# TRV_ANAREN_V0_3.net
KiCad netlist of a schematic drawn in EAGLE
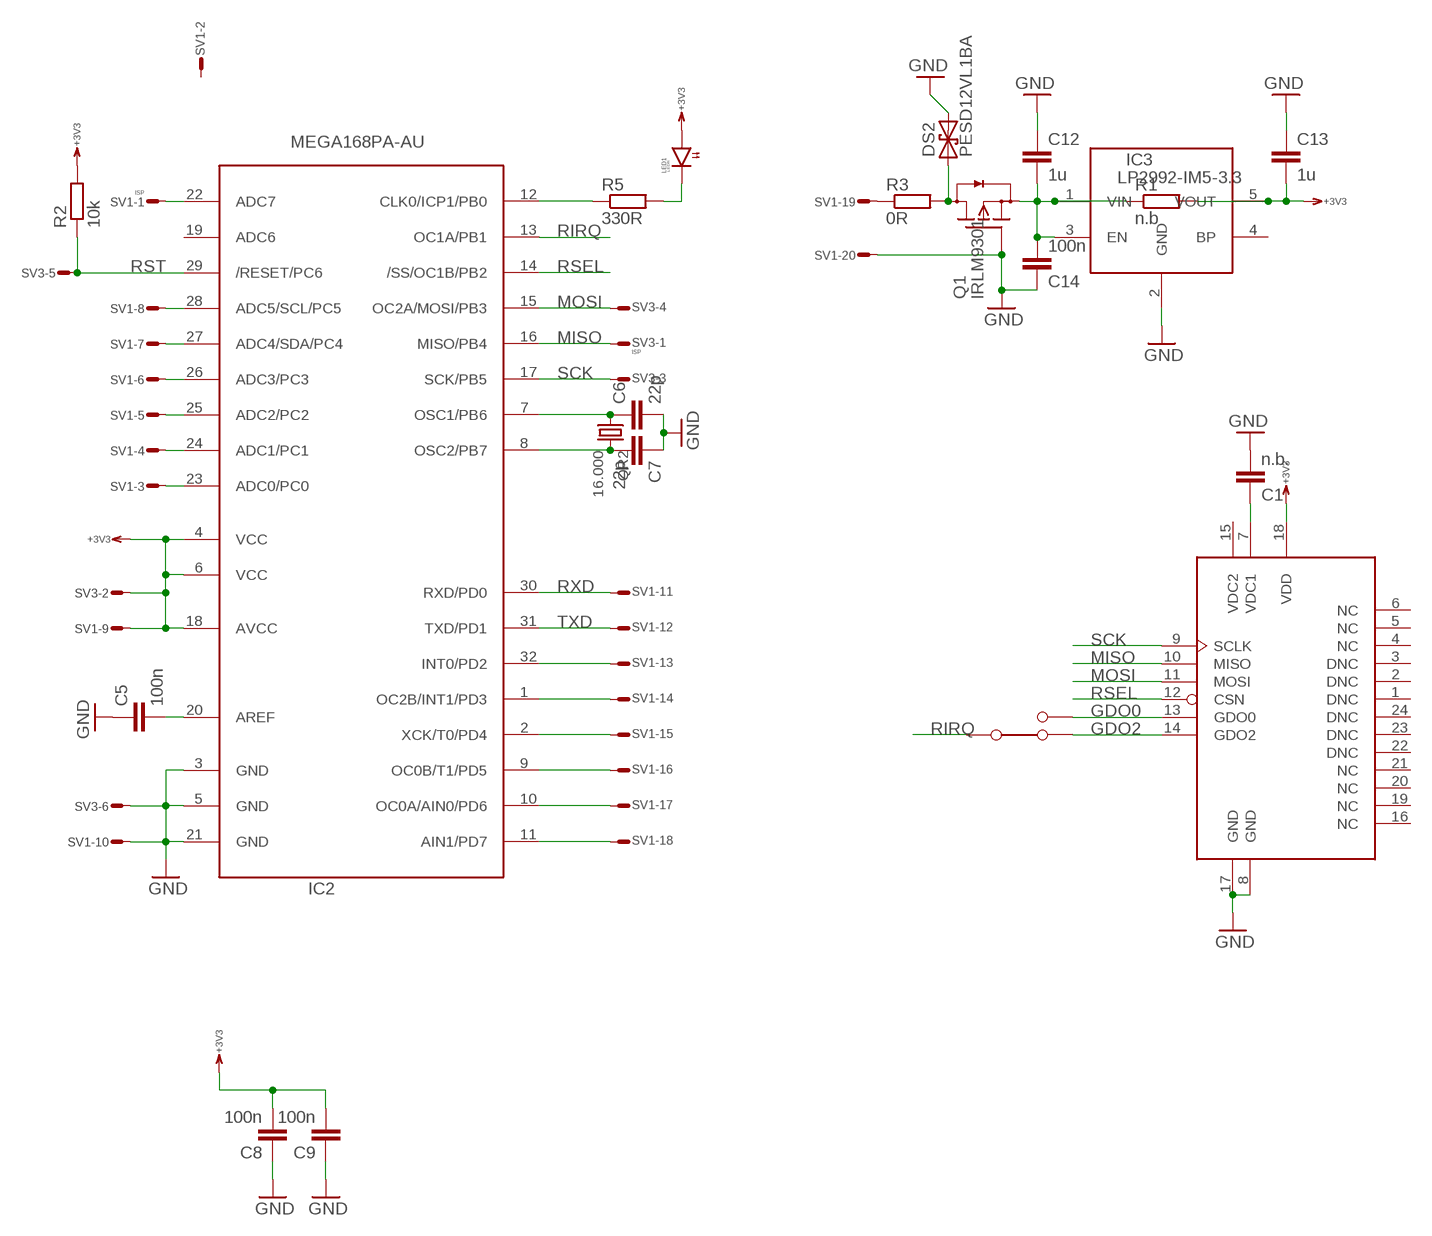
[diagram p0: schematic, sheet 1]

(export (version "E")
  (design (tool "Eeschema 10.0.6"))
  (components
    (comp (ref "BR1") (value "BR") (footprint "eagle-import:BR") (libsource (lib "eagle-import") (part "BR")))
    (comp (ref "C1")
      (value "n.b.")
      (footprint "eagle-import:0603")
      (libsource (lib "eagle-import") (part "C0603"))
    )
    (comp (ref "C5")
      (value "100n")
      (footprint "eagle-import:0603")
      (libsource (lib "eagle-import") (part "C0603"))
    )
    (comp (ref "C6")
      (value "22p")
      (footprint "eagle-import:0603")
      (libsource (lib "eagle-import") (part "C0603"))
    )
    (comp (ref "C7")
      (value "22p")
      (footprint "eagle-import:0603")
      (libsource (lib "eagle-import") (part "C0603"))
    )
    (comp (ref "C8")
      (value "100n")
      (footprint "eagle-import:0603")
      (libsource (lib "eagle-import") (part "C0603"))
    )
    (comp (ref "C9")
      (value "100n")
      (footprint "eagle-import:0603")
      (libsource (lib "eagle-import") (part "C0603"))
    )
    (comp (ref "C12")
      (value "1u")
      (footprint "eagle-import:0603")
      (libsource (lib "eagle-import") (part "C0603"))
    )
    (comp (ref "C13")
      (value "1u")
      (footprint "eagle-import:0603")
      (libsource (lib "eagle-import") (part "C0603"))
    )
    (comp (ref "C14")
      (value "100n")
      (footprint "eagle-import:0603")
      (libsource (lib "eagle-import") (part "C0603"))
    )
    (comp (ref "DS2")
      (value "PESD12VL1BA")
      (footprint "eagle-import:SOD323")
      (libsource (lib "eagle-import") (part "TVS-U323"))
    )
    (comp (ref "IC2")
      (value "MEGA168PA-AU")
      (footprint "eagle-import:TQFP32-08")
      (libsource (lib "eagle-import") (part "MEGA168PA"))
    )
    (comp (ref "IC3")
      (value "LP2992-IM5-3.3")
      (footprint "eagle-import:SOT23-5")
      (libsource (lib "eagle-import") (part "LDO"))
    )
    (comp (ref "LED1")
      (value "LEDR")
      (footprint "eagle-import:0603")
      (libsource (lib "eagle-import") (part "LED0603"))
    )
    (comp (ref "Q1")
      (value "IRLM9301")
      (footprint "eagle-import:SOT23")
      (libsource (lib "eagle-import") (part "FET-PDSOT23"))
    )
    (comp (ref "QR2")
      (value "16.000")
      (footprint "eagle-import:HC49U-V")
      (libsource (lib "eagle-import") (part "Q49UV"))
    )
    (comp (ref "R1")
      (value "n.b")
      (footprint "eagle-import:0603")
      (libsource (lib "eagle-import") (part "R0603"))
    )
    (comp (ref "R2")
      (value "10k")
      (footprint "eagle-import:0603")
      (libsource (lib "eagle-import") (part "R0603"))
    )
    (comp (ref "R3")
      (value "0R")
      (footprint "eagle-import:0603")
      (libsource (lib "eagle-import") (part "R0603"))
    )
    (comp (ref "R5")
      (value "330R")
      (footprint "eagle-import:0603")
      (libsource (lib "eagle-import") (part "R0603"))
    )
    (comp (ref "RF1")
      (value "ANARENC")
      (footprint "eagle-import:ANAREN_C")
      (libsource (lib "eagle-import") (part "ANARENC"))
    )
    (comp (ref "SV1")
      (value "ISP")
      (footprint "eagle-import:ML20")
      (libsource (lib "eagle-import") (part "ML20?E"))
    )
    (comp (ref "SV3")
      (value "ISP")
      (footprint "eagle-import:ML6")
      (libsource (lib "eagle-import") (part "ML6E"))
    )
  )
  (nets
    (net (code "1") (name "+3V3") (class "Default")
      (node (ref "C13") (pin "2") (pinfunction "2_2") (pintype "passive"))
      (node (ref "C8") (pin "2") (pinfunction "2_2") (pintype "passive"))
      (node (ref "C9") (pin "2") (pinfunction "2_2") (pintype "passive"))
      (node (ref "IC2") (pin "18") (pinfunction "AVCC_18") (pintype "bidirectional"))
      (node (ref "IC2") (pin "4") (pinfunction "VCC_4") (pintype "bidirectional"))
      (node (ref "IC2") (pin "6") (pinfunction "VCC_6") (pintype "bidirectional"))
      (node (ref "IC3") (pin "5") (pinfunction "VOUT_5") (pintype "bidirectional"))
      (node (ref "LED1") (pin "1") (pinfunction "A_1") (pintype "bidirectional"))
      (node (ref "R1") (pin "2") (pinfunction "2_2") (pintype "passive"))
      (node (ref "R2") (pin "2") (pinfunction "2_2") (pintype "passive"))
      (node (ref "RF1") (pin "18") (pinfunction "VDD_18") (pintype "bidirectional"))
      (node (ref "SV1") (pin "9") (pinfunction "S_9") (pintype "passive"))
      (node (ref "SV3") (pin "2") (pinfunction "S_2") (pintype "passive"))
    )
    (net (code "2") (name "/GDO0") (class "Default")
      (node (ref "BR1") (pin "R") (pinfunction "R_R") (pintype "bidirectional"))
      (node (ref "RF1") (pin "13") (pinfunction "GDO0_13") (pintype "bidirectional"))
    )
    (net (code "3") (name "/GDO2") (class "Default")
      (node (ref "BR1") (pin "L") (pinfunction "L_L") (pintype "bidirectional"))
      (node (ref "RF1") (pin "14") (pinfunction "GDO2_14") (pintype "bidirectional"))
    )
    (net (code "4") (name "/MISO") (class "Default")
      (node (ref "IC2") (pin "16") (pinfunction "MISO/PB4_16") (pintype "bidirectional"))
      (node (ref "RF1") (pin "10") (pinfunction "MISO_10") (pintype "output"))
      (node (ref "SV3") (pin "1") (pinfunction "S_1") (pintype "passive"))
    )
    (net (code "5") (name "/MOSI") (class "Default")
      (node (ref "IC2") (pin "15") (pinfunction "OC2A/MOSI/PB3_15") (pintype "bidirectional"))
      (node (ref "RF1") (pin "11") (pinfunction "MOSI_11") (pintype "input"))
      (node (ref "SV3") (pin "4") (pinfunction "S_4") (pintype "passive"))
    )
    (net (code "6") (name "/RIRQ") (class "Default")
      (node (ref "BR1") (pin "M") (pinfunction "M_M") (pintype "bidirectional"))
      (node (ref "IC2") (pin "13") (pinfunction "OC1A/PB1_13") (pintype "bidirectional"))
    )
    (net (code "7") (name "/RSEL") (class "Default")
      (node (ref "IC2") (pin "14") (pinfunction "/SS/OC1B/PB2_14") (pintype "bidirectional"))
      (node (ref "RF1") (pin "12") (pinfunction "CSN_12") (pintype "input"))
    )
    (net (code "8") (name "/RST") (class "Default")
      (node (ref "IC2") (pin "29") (pinfunction "/RESET/PC6_29") (pintype "bidirectional"))
      (node (ref "R2") (pin "1") (pinfunction "1_1") (pintype "passive"))
      (node (ref "SV3") (pin "5") (pinfunction "S_5") (pintype "passive"))
    )
    (net (code "9") (name "/RXD") (class "Default")
      (node (ref "IC2") (pin "30") (pinfunction "RXD/PD0_30") (pintype "bidirectional"))
      (node (ref "SV1") (pin "11") (pinfunction "S_11") (pintype "passive"))
    )
    (net (code "10") (name "/SCK") (class "Default")
      (node (ref "IC2") (pin "17") (pinfunction "SCK/PB5_17") (pintype "bidirectional"))
      (node (ref "RF1") (pin "9") (pinfunction "SCLK_9") (pintype "input"))
      (node (ref "SV3") (pin "3") (pinfunction "S_3") (pintype "passive"))
    )
    (net (code "11") (name "/TXD") (class "Default")
      (node (ref "IC2") (pin "31") (pinfunction "TXD/PD1_31") (pintype "bidirectional"))
      (node (ref "SV1") (pin "12") (pinfunction "S_12") (pintype "passive"))
    )
    (net (code "12") (name "GND") (class "Default")
      (node (ref "C1") (pin "2") (pinfunction "2_2") (pintype "passive"))
      (node (ref "C12") (pin "1") (pinfunction "1_1") (pintype "passive"))
      (node (ref "C13") (pin "1") (pinfunction "1_1") (pintype "passive"))
      (node (ref "C14") (pin "1") (pinfunction "1_1") (pintype "passive"))
      (node (ref "C5") (pin "1") (pinfunction "1_1") (pintype "passive"))
      (node (ref "C6") (pin "2") (pinfunction "2_2") (pintype "passive"))
      (node (ref "C7") (pin "1") (pinfunction "1_1") (pintype "passive"))
      (node (ref "C8") (pin "1") (pinfunction "1_1") (pintype "passive"))
      (node (ref "C9") (pin "1") (pinfunction "1_1") (pintype "passive"))
      (node (ref "DS2") (pin "C") (pinfunction "2_C") (pintype "passive"))
      (node (ref "IC2") (pin "21") (pinfunction "GND_21") (pintype "bidirectional"))
      (node (ref "IC2") (pin "3") (pinfunction "GND_3") (pintype "bidirectional"))
      (node (ref "IC2") (pin "5") (pinfunction "GND_5") (pintype "bidirectional"))
      (node (ref "IC3") (pin "2") (pinfunction "GND_2") (pintype "bidirectional"))
      (node (ref "Q1") (pin "1") (pinfunction "G_1") (pintype "passive"))
      (node (ref "RF1") (pin "17") (pinfunction "GND_17") (pintype "bidirectional"))
      (node (ref "RF1") (pin "8") (pinfunction "GND_8") (pintype "bidirectional"))
      (node (ref "SV1") (pin "10") (pinfunction "S_10") (pintype "passive"))
      (node (ref "SV1") (pin "20") (pinfunction "S_20") (pintype "passive"))
      (node (ref "SV3") (pin "6") (pinfunction "S_6") (pintype "passive"))
    )
    (net (code "13") (name "Net-(DS2-1)") (class "Default")
      (node (ref "DS2") (pin "A") (pinfunction "1_A") (pintype "passive"))
      (node (ref "Q1") (pin "3") (pinfunction "D_3") (pintype "passive"))
      (node (ref "R3") (pin "2") (pinfunction "2_2") (pintype "passive"))
    )
    (net (code "14") (name "Net-(IC2-ADC0{slash}PC0)") (class "Default")
      (node (ref "IC2") (pin "23") (pinfunction "ADC0/PC0_23") (pintype "bidirectional"))
      (node (ref "SV1") (pin "3") (pinfunction "S_3") (pintype "passive"))
    )
    (net (code "15") (name "Net-(IC2-ADC1{slash}PC1)") (class "Default")
      (node (ref "IC2") (pin "24") (pinfunction "ADC1/PC1_24") (pintype "bidirectional"))
      (node (ref "SV1") (pin "4") (pinfunction "S_4") (pintype "passive"))
    )
    (net (code "16") (name "Net-(IC2-ADC2{slash}PC2)") (class "Default")
      (node (ref "IC2") (pin "25") (pinfunction "ADC2/PC2_25") (pintype "bidirectional"))
      (node (ref "SV1") (pin "5") (pinfunction "S_5") (pintype "passive"))
    )
    (net (code "17") (name "Net-(IC2-ADC3{slash}PC3)") (class "Default")
      (node (ref "IC2") (pin "26") (pinfunction "ADC3/PC3_26") (pintype "bidirectional"))
      (node (ref "SV1") (pin "6") (pinfunction "S_6") (pintype "passive"))
    )
    (net (code "18") (name "Net-(IC2-ADC4{slash}SDA{slash}PC4)") (class "Default")
      (node (ref "IC2") (pin "27") (pinfunction "ADC4/SDA/PC4_27") (pintype "bidirectional"))
      (node (ref "SV1") (pin "7") (pinfunction "S_7") (pintype "passive"))
    )
    (net (code "19") (name "Net-(IC2-ADC5{slash}SCL{slash}PC5)") (class "Default")
      (node (ref "IC2") (pin "28") (pinfunction "ADC5/SCL/PC5_28") (pintype "bidirectional"))
      (node (ref "SV1") (pin "8") (pinfunction "S_8") (pintype "passive"))
    )
    (net (code "20") (name "Net-(IC2-ADC7)") (class "Default")
      (node (ref "IC2") (pin "22") (pinfunction "ADC7_22") (pintype "bidirectional"))
      (node (ref "SV1") (pin "1") (pinfunction "S_1") (pintype "passive"))
    )
    (net (code "21") (name "Net-(IC2-AIN1{slash}PD7)") (class "Default")
      (node (ref "IC2") (pin "11") (pinfunction "AIN1/PD7_11") (pintype "bidirectional"))
      (node (ref "SV1") (pin "18") (pinfunction "S_18") (pintype "passive"))
    )
    (net (code "22") (name "Net-(IC2-AREF)") (class "Default")
      (node (ref "C5") (pin "2") (pinfunction "2_2") (pintype "passive"))
      (node (ref "IC2") (pin "20") (pinfunction "AREF_20") (pintype "bidirectional"))
    )
    (net (code "23") (name "Net-(IC2-CLK0{slash}ICP1{slash}PB0)") (class "Default")
      (node (ref "IC2") (pin "12") (pinfunction "CLK0/ICP1/PB0_12") (pintype "bidirectional"))
      (node (ref "R5") (pin "1") (pinfunction "1_1") (pintype "passive"))
    )
    (net (code "24") (name "Net-(IC2-INT0{slash}PD2)") (class "Default")
      (node (ref "IC2") (pin "32") (pinfunction "INT0/PD2_32") (pintype "bidirectional"))
      (node (ref "SV1") (pin "13") (pinfunction "S_13") (pintype "passive"))
    )
    (net (code "25") (name "Net-(IC2-OC0A{slash}AIN0{slash}PD6)") (class "Default")
      (node (ref "IC2") (pin "10") (pinfunction "OC0A/AIN0/PD6_10") (pintype "bidirectional"))
      (node (ref "SV1") (pin "17") (pinfunction "S_17") (pintype "passive"))
    )
    (net (code "26") (name "Net-(IC2-OC0B{slash}T1{slash}PD5)") (class "Default")
      (node (ref "IC2") (pin "9") (pinfunction "OC0B/T1/PD5_9") (pintype "bidirectional"))
      (node (ref "SV1") (pin "16") (pinfunction "S_16") (pintype "passive"))
    )
    (net (code "27") (name "Net-(IC2-OC2B{slash}INT1{slash}PD3)") (class "Default")
      (node (ref "IC2") (pin "1") (pinfunction "OC2B/INT1/PD3_1") (pintype "bidirectional"))
      (node (ref "SV1") (pin "14") (pinfunction "S_14") (pintype "passive"))
    )
    (net (code "28") (name "Net-(IC2-OSC1{slash}PB6)") (class "Default")
      (node (ref "C6") (pin "1") (pinfunction "1_1") (pintype "passive"))
      (node (ref "IC2") (pin "7") (pinfunction "OSC1/PB6_7") (pintype "bidirectional"))
      (node (ref "QR2") (pin "1") (pinfunction "1_1") (pintype "passive"))
    )
    (net (code "29") (name "Net-(IC2-OSC2{slash}PB7)") (class "Default")
      (node (ref "C7") (pin "2") (pinfunction "2_2") (pintype "passive"))
      (node (ref "IC2") (pin "8") (pinfunction "OSC2/PB7_8") (pintype "bidirectional"))
      (node (ref "QR2") (pin "2") (pinfunction "2_2") (pintype "passive"))
    )
    (net (code "30") (name "Net-(IC2-XCK{slash}T0{slash}PD4)") (class "Default")
      (node (ref "IC2") (pin "2") (pinfunction "XCK/T0/PD4_2") (pintype "bidirectional"))
      (node (ref "SV1") (pin "15") (pinfunction "S_15") (pintype "passive"))
    )
    (net (code "31") (name "Net-(IC3-EN)") (class "Default")
      (node (ref "C12") (pin "2") (pinfunction "2_2") (pintype "passive"))
      (node (ref "C14") (pin "2") (pinfunction "2_2") (pintype "passive"))
      (node (ref "IC3") (pin "1") (pinfunction "VIN_1") (pintype "bidirectional"))
      (node (ref "IC3") (pin "3") (pinfunction "EN_3") (pintype "bidirectional"))
      (node (ref "Q1") (pin "2") (pinfunction "S_2") (pintype "passive"))
      (node (ref "R1") (pin "1") (pinfunction "1_1") (pintype "passive"))
    )
    (net (code "32") (name "Net-(LED1-C)") (class "Default")
      (node (ref "LED1") (pin "2") (pinfunction "C_2") (pintype "bidirectional"))
      (node (ref "R5") (pin "2") (pinfunction "2_2") (pintype "passive"))
    )
    (net (code "33") (name "Net-(RF1-VDC1)") (class "Default")
      (node (ref "C1") (pin "1") (pinfunction "1_1") (pintype "passive"))
      (node (ref "RF1") (pin "7") (pinfunction "VDC1_7") (pintype "bidirectional"))
    )
    (net (code "34") (name "Net-(SV1K-S)") (class "Default")
      (node (ref "R3") (pin "1") (pinfunction "1_1") (pintype "passive"))
      (node (ref "SV1") (pin "19") (pinfunction "S_19") (pintype "passive"))
    )
    (net (code "35") (name "unconnected-(IC2-ADC6-Pad19)") (class "Default")
      (node (ref "IC2") (pin "19") (pinfunction "ADC6_19") (pintype "bidirectional"))
    )
    (net (code "36") (name "unconnected-(IC3-BP-Pad4)") (class "Default")
      (node (ref "IC3") (pin "4") (pinfunction "BP_4") (pintype "bidirectional"))
    )
    (net (code "37") (name "unconnected-(RF1-DNC-Pad1)") (class "Default")
      (node (ref "RF1") (pin "1") (pinfunction "DNC_1") (pintype "bidirectional"))
    )
    (net (code "38") (name "unconnected-(RF1-DNC-Pad2)") (class "Default")
      (node (ref "RF1") (pin "2") (pinfunction "DNC_2") (pintype "bidirectional"))
    )
    (net (code "39") (name "unconnected-(RF1-DNC-Pad3)") (class "Default")
      (node (ref "RF1") (pin "3") (pinfunction "DNC_3") (pintype "bidirectional"))
    )
    (net (code "40") (name "unconnected-(RF1-DNC-Pad22)") (class "Default")
      (node (ref "RF1") (pin "22") (pinfunction "DNC_22") (pintype "bidirectional"))
    )
    (net (code "41") (name "unconnected-(RF1-DNC-Pad23)") (class "Default")
      (node (ref "RF1") (pin "23") (pinfunction "DNC_23") (pintype "bidirectional"))
    )
    (net (code "42") (name "unconnected-(RF1-DNC-Pad24)") (class "Default")
      (node (ref "RF1") (pin "24") (pinfunction "DNC_24") (pintype "bidirectional"))
    )
    (net (code "43") (name "unconnected-(RF1-NC-Pad4)") (class "Default")
      (node (ref "RF1") (pin "4") (pinfunction "NC_4") (pintype "bidirectional"))
    )
    (net (code "44") (name "unconnected-(RF1-NC-Pad5)") (class "Default")
      (node (ref "RF1") (pin "5") (pinfunction "NC_5") (pintype "bidirectional"))
    )
    (net (code "45") (name "unconnected-(RF1-NC-Pad6)") (class "Default")
      (node (ref "RF1") (pin "6") (pinfunction "NC_6") (pintype "bidirectional"))
    )
    (net (code "46") (name "unconnected-(RF1-NC-Pad16)") (class "Default")
      (node (ref "RF1") (pin "16") (pinfunction "NC_16") (pintype "bidirectional"))
    )
    (net (code "47") (name "unconnected-(RF1-NC-Pad19)") (class "Default")
      (node (ref "RF1") (pin "19") (pinfunction "NC_19") (pintype "bidirectional"))
    )
    (net (code "48") (name "unconnected-(RF1-NC-Pad20)") (class "Default")
      (node (ref "RF1") (pin "20") (pinfunction "NC_20") (pintype "bidirectional"))
    )
    (net (code "49") (name "unconnected-(RF1-NC-Pad21)") (class "Default")
      (node (ref "RF1") (pin "21") (pinfunction "NC_21") (pintype "bidirectional"))
    )
    (net (code "50") (name "unconnected-(RF1-VDC2-Pad15)") (class "Default")
      (node (ref "RF1") (pin "15") (pinfunction "VDC2_15") (pintype "bidirectional"))
    )
    (net (code "51") (name "unconnected-(SV1L-S-Pad2)") (class "Default")
      (node (ref "SV1") (pin "2") (pinfunction "S_2") (pintype "passive"))
    )
  )
)
